# PDB.net
KiCad netlist of a schematic drawn in EAGLE
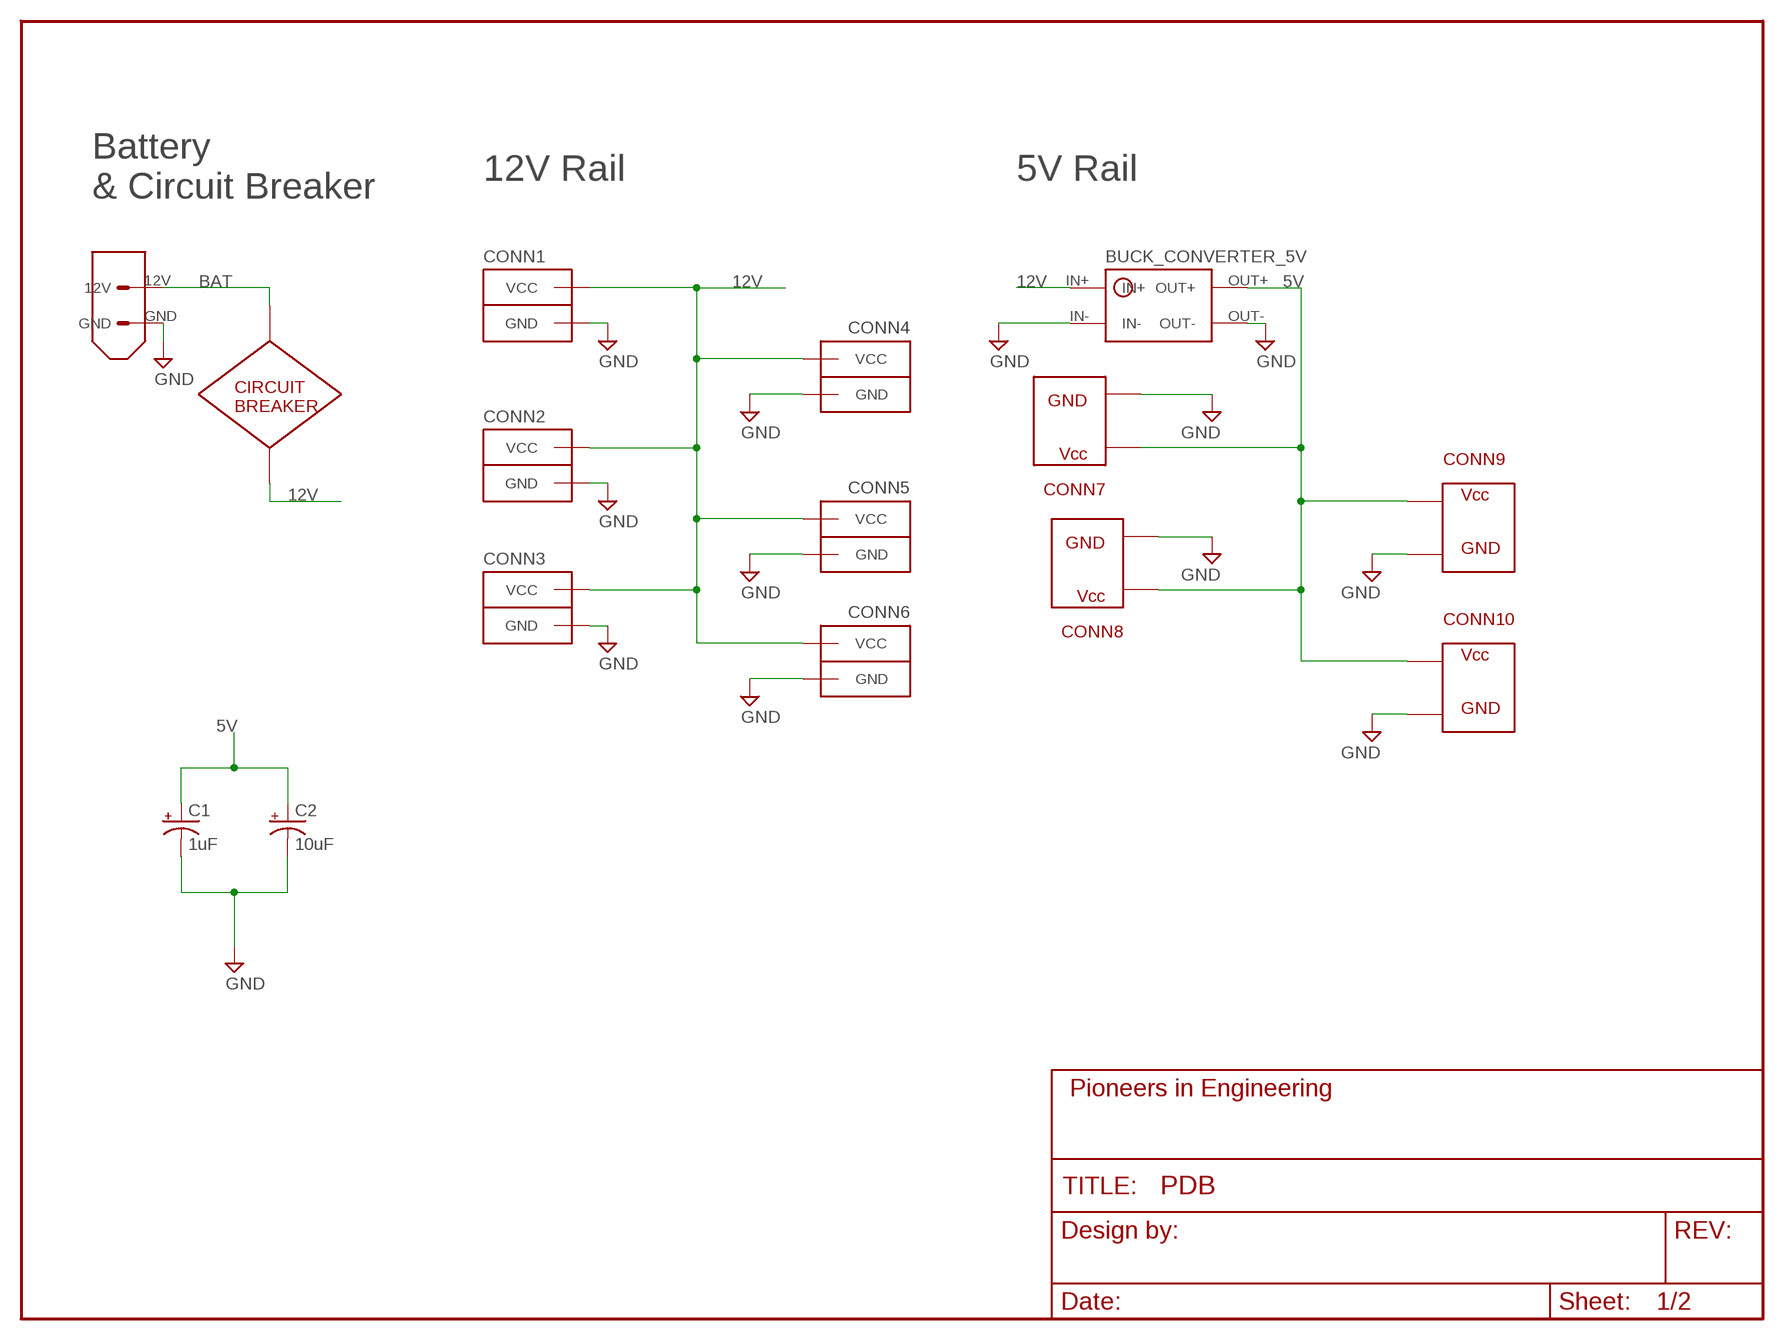
[diagram p0: schematic, sheet 1]
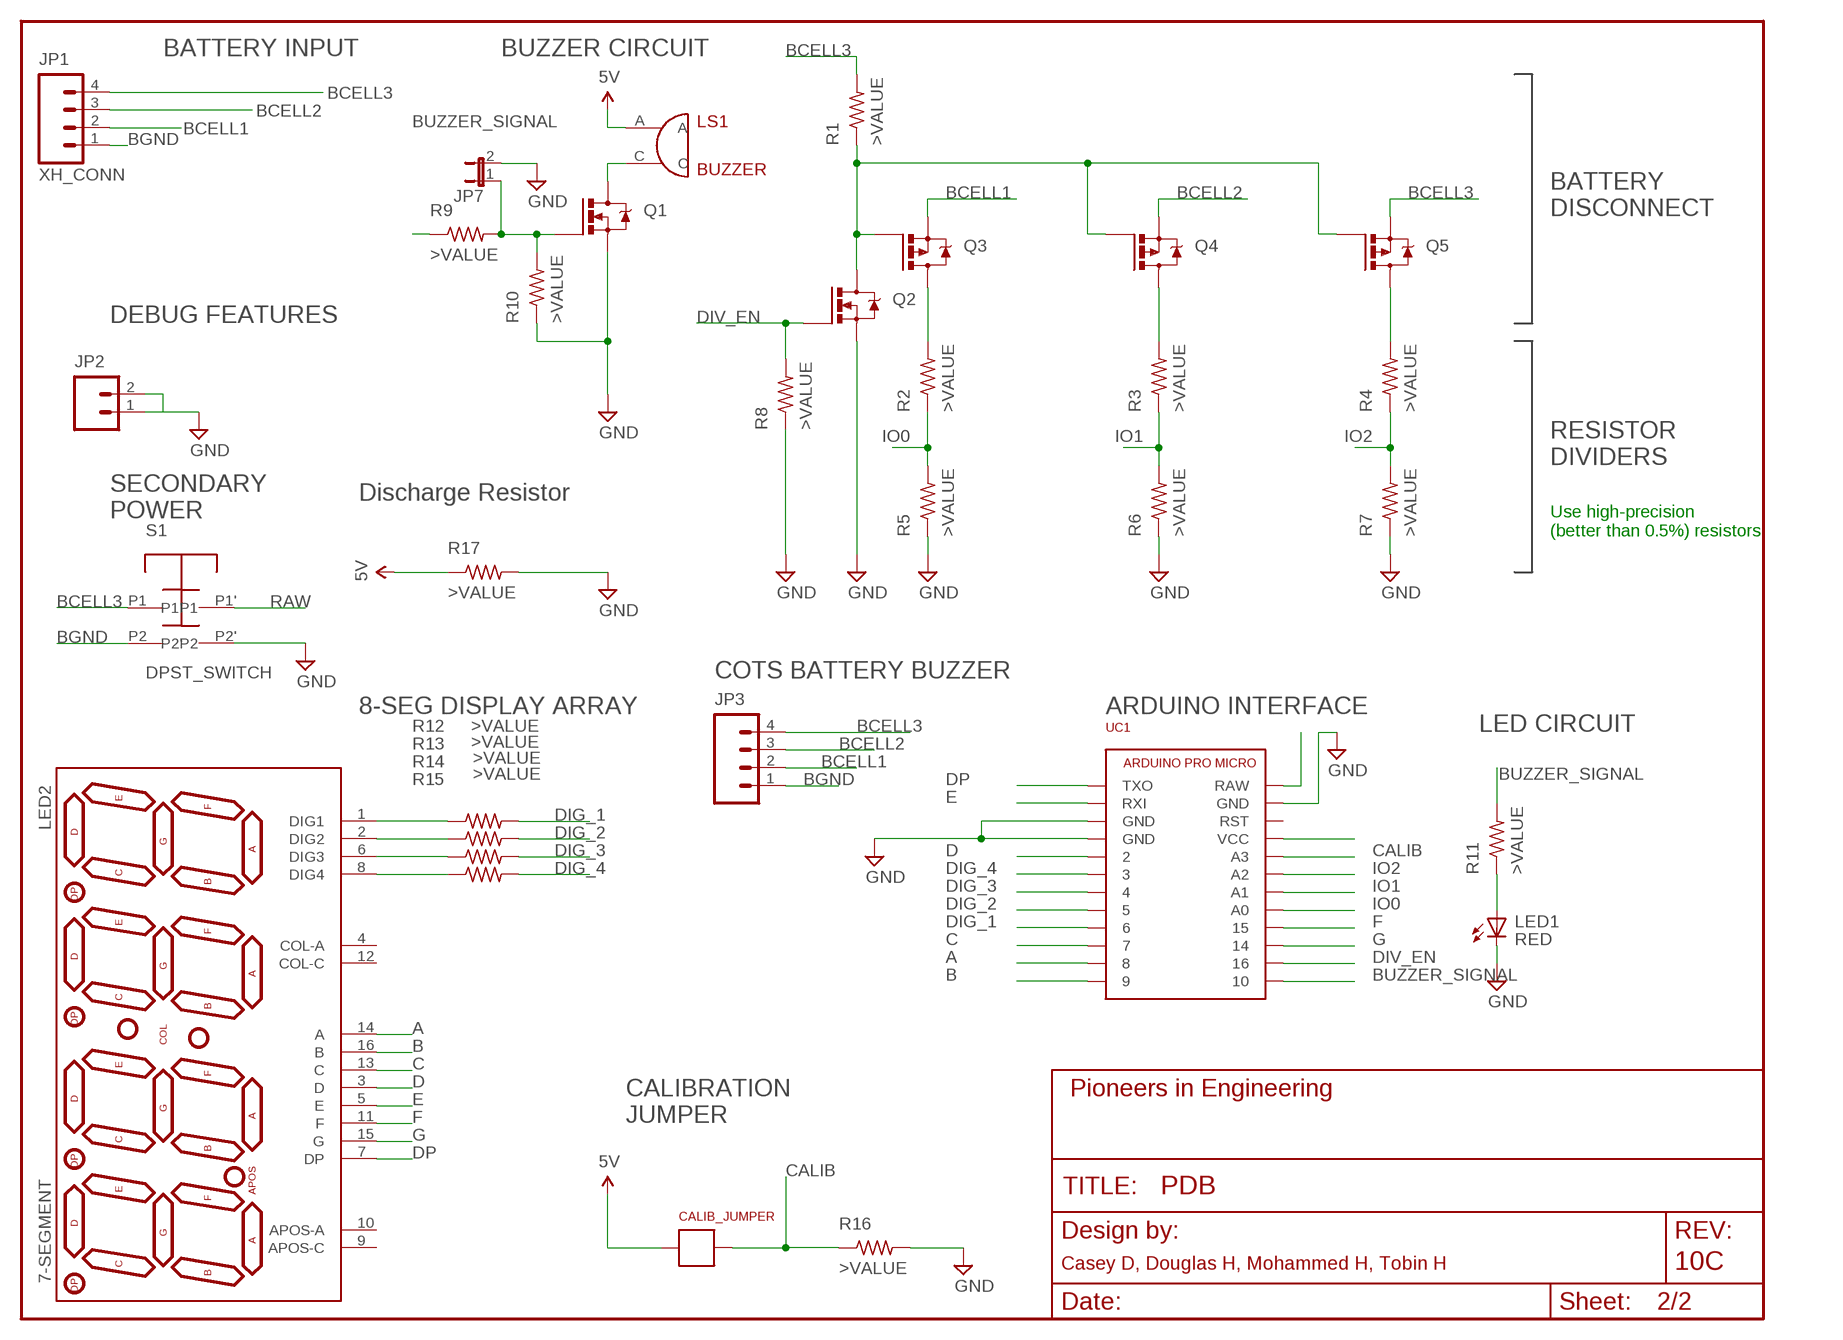
[diagram p1: schematic, sheet 2]

(export (version "E")
  (design (tool "Eeschema 10.0.6"))
  (components
    (comp (ref "CALIB_JUMPER")
      (value "JUMPER")
      (footprint "eagle-import:JUMPER")
      (fields
        (field (name "DISTRIBUTOR_PART_NUMBER") "952-2262-ND")
        (field (name "MANUFACTURER") "Harwin. Inc")
        (field (name "MANUFACTURER_PART_NUMBER") "M20-9990246")
      )
      (libsource (lib "eagle-import") (part "JUMPER"))
    )
    (comp (ref "JP1")
      (value "XH_CONN")
      (footprint "eagle-import:XH_CONNECTOR_4POS_2.5MM")
      (libsource (lib "eagle-import") (part "XH_CONNECTOR_4POS"))
    )
    (comp (ref "JP2")
      (value "M02PTH")
      (footprint "eagle-import:1X02")
      (libsource (lib "eagle-import") (part "M02PTH"))
    )
    (comp (ref "JP3")
      (value "M04PTH")
      (footprint "eagle-import:1X04")
      (libsource (lib "eagle-import") (part "M04PTH"))
    )
    (comp (ref "JP7")
      (value "JP1E")
      (footprint "eagle-import:JP1")
      (libsource (lib "eagle-import") (part "JP1E"))
    )
    (comp (ref "LED1")
      (value "RED")
      (footprint "eagle-import:LED-0805")
      (libsource (lib "eagle-import") (part "LED0805"))
    )
    (comp (ref "LED2")
      (value "7-SEGMENT")
      (footprint "eagle-import:7-SEGMENT-4DIGIT-YOUNGSUN")
      (libsource (lib "eagle-import") (part "7-SEGMENT-4DIGIT-YOUNGSUN"))
    )
    (comp (ref "LS1")
      (value "BUZZER")
      (footprint "eagle-import:BUZZER_MAGNETIC_5V_12MM_RADIAL")
      (libsource (lib "eagle-import") (part "BUZZER"))
    )
    (comp (ref "Q1")
      (value "NMOS")
      (footprint "eagle-import:SOT23-3")
      (libsource (lib "eagle-import") (part "N-CHANNEL-MOSFETSOT23-3"))
    )
    (comp (ref "Q2")
      (value "IRFML8244")
      (footprint "eagle-import:SOT23-3")
      (libsource (lib "eagle-import") (part "N-CHANNEL-MOSFETSOT23-3"))
    )
    (comp (ref "Q3")
      (value "PMOS")
      (footprint "eagle-import:SOT23-3")
      (libsource (lib "eagle-import") (part "P-CHANNEL-MOSFETSOT23-3"))
    )
    (comp (ref "Q4")
      (value "PMOS")
      (footprint "eagle-import:SOT23-3")
      (libsource (lib "eagle-import") (part "P-CHANNEL-MOSFETSOT23-3"))
    )
    (comp (ref "Q5")
      (value "PMOS")
      (footprint "eagle-import:SOT23-3")
      (libsource (lib "eagle-import") (part "P-CHANNEL-MOSFETSOT23-3"))
    )
    (comp (ref "R1")
      (value ">VALUE")
      (footprint "eagle-import:R0603")
      (fields (field (name "MANUFACTURER") "Rohm Semiconductor"))
      (libsource (lib "eagle-import") (part "R-US_R0603"))
    )
    (comp (ref "R2")
      (value ">VALUE")
      (footprint "eagle-import:R0603")
      (fields (field (name "MANUFACTURER") "Rohm Semiconductor"))
      (libsource (lib "eagle-import") (part "R-US_R0603"))
    )
    (comp (ref "R3")
      (value ">VALUE")
      (footprint "eagle-import:R0603")
      (fields (field (name "MANUFACTURER") "Rohm Semiconductor"))
      (libsource (lib "eagle-import") (part "R-US_R0603"))
    )
    (comp (ref "R4")
      (value ">VALUE")
      (footprint "eagle-import:R0603")
      (fields (field (name "MANUFACTURER") "Rohm Semiconductor"))
      (libsource (lib "eagle-import") (part "R-US_R0603"))
    )
    (comp (ref "R5")
      (value ">VALUE")
      (footprint "eagle-import:R0603")
      (fields (field (name "MANUFACTURER") "Rohm Semiconductor"))
      (libsource (lib "eagle-import") (part "R-US_R0603"))
    )
    (comp (ref "R6")
      (value ">VALUE")
      (footprint "eagle-import:R0603")
      (fields (field (name "MANUFACTURER") "Rohm Semiconductor"))
      (libsource (lib "eagle-import") (part "R-US_R0603"))
    )
    (comp (ref "R7")
      (value ">VALUE")
      (footprint "eagle-import:R0603")
      (fields (field (name "MANUFACTURER") "Rohm Semiconductor"))
      (libsource (lib "eagle-import") (part "R-US_R0603"))
    )
    (comp (ref "R8")
      (value ">VALUE")
      (footprint "eagle-import:R0603")
      (fields (field (name "MANUFACTURER") "Rohm Semiconductor"))
      (libsource (lib "eagle-import") (part "R-US_R0603"))
    )
    (comp (ref "R9")
      (value ">VALUE")
      (footprint "eagle-import:R0603")
      (fields (field (name "MANUFACTURER") "Rohm Semiconductor"))
      (libsource (lib "eagle-import") (part "R-US_R0603"))
    )
    (comp (ref "R10")
      (value ">VALUE")
      (footprint "eagle-import:R0603")
      (fields (field (name "MANUFACTURER") "Rohm Semiconductor"))
      (libsource (lib "eagle-import") (part "R-US_R0603"))
    )
    (comp (ref "R11")
      (value ">VALUE")
      (footprint "eagle-import:R0603")
      (fields (field (name "MANUFACTURER") "Rohm Semiconductor"))
      (libsource (lib "eagle-import") (part "R-US_R0603"))
    )
    (comp (ref "R12")
      (value ">VALUE")
      (footprint "eagle-import:R0603")
      (fields (field (name "MANUFACTURER") "Rohm Semiconductor"))
      (libsource (lib "eagle-import") (part "R-US_R0603"))
    )
    (comp (ref "R13")
      (value ">VALUE")
      (footprint "eagle-import:R0603")
      (fields (field (name "MANUFACTURER") "Rohm Semiconductor"))
      (libsource (lib "eagle-import") (part "R-US_R0603"))
    )
    (comp (ref "R14")
      (value ">VALUE")
      (footprint "eagle-import:R0603")
      (fields (field (name "MANUFACTURER") "Rohm Semiconductor"))
      (libsource (lib "eagle-import") (part "R-US_R0603"))
    )
    (comp (ref "R15")
      (value ">VALUE")
      (footprint "eagle-import:R0603")
      (fields (field (name "MANUFACTURER") "Rohm Semiconductor"))
      (libsource (lib "eagle-import") (part "R-US_R0603"))
    )
    (comp (ref "R16")
      (value ">VALUE")
      (footprint "eagle-import:R0603")
      (fields (field (name "MANUFACTURER") "Rohm Semiconductor"))
      (libsource (lib "eagle-import") (part "R-US_R0603"))
    )
    (comp (ref "R17")
      (value ">VALUE")
      (footprint "eagle-import:R0603")
      (fields (field (name "MANUFACTURER") "Rohm Semiconductor"))
      (libsource (lib "eagle-import") (part "R-US_R0603"))
    )
    (comp (ref "S1")
      (value "DPST_SWITCH")
      (footprint "eagle-import:C&K_SWITCH")
      (libsource (lib "eagle-import") (part "DPST_SWITCH"))
    )
    (comp (ref "UC1")
      (value "ARDUINO_PRO_MICRO")
      (footprint "eagle-import:ARDUINO_PRO_MICRO")
      (fields
        (field (name "DISTRIBUTOR_PART_NUMBER") "32284746884")
        (field (name "MANUFACTURER") "Feiyang electronics")
      )
      (libsource (lib "eagle-import") (part "ARDUINO_PRO_MICRO"))
    )
    (comp (ref "C1")
      (value "1uF")
      (footprint "eagle-import:E5-5")
      (libsource (lib "eagle-import") (part "CPOL-USE5-5"))
    )
    (comp (ref "C2")
      (value "10uF")
      (footprint "eagle-import:E5-5")
      (libsource (lib "eagle-import") (part "CPOL-USE5-5"))
    )
    (comp (ref "CIRCUIT_BREAKER")
      (value "CIRC_BREAKER")
      (footprint "eagle-import:CIRC_BREAKER")
      (libsource (lib "eagle-import") (part "CIRC_BREAKER"))
    )
    (comp (ref "CONN1")
      (value "ANDERSONVERTICAL")
      (footprint "eagle-import:ANDERSON_VERTICAL")
      (libsource (lib "eagle-import") (part "ANDERSONVERTICAL"))
    )
    (comp (ref "CONN2")
      (value "ANDERSONVERTICAL")
      (footprint "eagle-import:ANDERSON_VERTICAL")
      (libsource (lib "eagle-import") (part "ANDERSONVERTICAL"))
    )
    (comp (ref "CONN3")
      (value "ANDERSONVERTICAL")
      (footprint "eagle-import:ANDERSON_VERTICAL")
      (libsource (lib "eagle-import") (part "ANDERSONVERTICAL"))
    )
    (comp (ref "CONN4")
      (value "ANDERSONVERTICAL")
      (footprint "eagle-import:ANDERSON_VERTICAL")
      (libsource (lib "eagle-import") (part "ANDERSONVERTICAL"))
    )
    (comp (ref "CONN5")
      (value "ANDERSONVERTICAL")
      (footprint "eagle-import:ANDERSON_VERTICAL")
      (libsource (lib "eagle-import") (part "ANDERSONVERTICAL"))
    )
    (comp (ref "CONN6")
      (value "ANDERSONVERTICAL")
      (footprint "eagle-import:ANDERSON_VERTICAL")
      (libsource (lib "eagle-import") (part "ANDERSONVERTICAL"))
    )
    (comp (ref "CONN7")
      (value "ATX")
      (footprint "eagle-import:ATX")
      (libsource (lib "eagle-import") (part "ATX"))
    )
    (comp (ref "CONN8")
      (value "ATX")
      (footprint "eagle-import:ATX")
      (libsource (lib "eagle-import") (part "ATX"))
    )
    (comp (ref "CONN9")
      (value "ATX")
      (footprint "eagle-import:ATX")
      (libsource (lib "eagle-import") (part "ATX"))
    )
    (comp (ref "CONN10")
      (value "ATX")
      (footprint "eagle-import:ATX")
      (libsource (lib "eagle-import") (part "ATX"))
    )
    (comp (ref "U$1")
      (value "BUCK_CONVERTER_5V")
      (footprint "eagle-import:BUCK_CONVERTER_5V")
      (libsource (lib "eagle-import") (part "BUCK_CONVERTER_5V"))
    )
    (comp (ref "XT60")
      (value "XT60CONNECTOR")
      (footprint "eagle-import:XT60CONNECTOR")
      (fields (field (name "PARTNUMBER") "PRT-10474 "))
      (libsource (lib "eagle-import") (part "XT60CONNECTOR"))
    )
  )
  (nets
    (net (code "1") (name "5V") (class "Default")
      (node (ref "C1") (pin "+") (pinfunction "+_+") (pintype "passive"))
      (node (ref "C2") (pin "+") (pinfunction "+_+") (pintype "passive"))
      (node (ref "CALIB_JUMPER") (pin "P$1") (pinfunction "P$1_P$1") (pintype "input"))
      (node (ref "CONN10") (pin "P$1") (pinfunction "P$1_P$1") (pintype "power_in"))
      (node (ref "CONN7") (pin "P$1") (pinfunction "P$1_P$1") (pintype "power_in"))
      (node (ref "CONN8") (pin "P$1") (pinfunction "P$1_P$1") (pintype "power_in"))
      (node (ref "CONN9") (pin "P$1") (pinfunction "P$1_P$1") (pintype "power_in"))
      (node (ref "LS1") (pin "A") (pinfunction "A_A") (pintype "bidirectional"))
      (node (ref "R17") (pin "1") (pinfunction "1_1") (pintype "passive"))
      (node (ref "U$1") (pin "OUT+") (pinfunction "OUT+_OUT+") (pintype "bidirectional"))
      (node (ref "UC1") (pin "VCC") (pinfunction "VCC_VCC") (pintype "bidirectional"))
    )
    (net (code "2") (name "12V") (class "Default")
      (node (ref "CIRCUIT_BREAKER") (pin "P$2") (pinfunction "P$2_P$2") (pintype "bidirectional"))
      (node (ref "CONN1") (pin "PIN2") (pinfunction "VCC_PIN2") (pintype "bidirectional"))
      (node (ref "CONN2") (pin "PIN2") (pinfunction "VCC_PIN2") (pintype "bidirectional"))
      (node (ref "CONN3") (pin "PIN2") (pinfunction "VCC_PIN2") (pintype "bidirectional"))
      (node (ref "CONN4") (pin "PIN2") (pinfunction "VCC_PIN2") (pintype "bidirectional"))
      (node (ref "CONN5") (pin "PIN2") (pinfunction "VCC_PIN2") (pintype "bidirectional"))
      (node (ref "CONN6") (pin "PIN2") (pinfunction "VCC_PIN2") (pintype "bidirectional"))
      (node (ref "U$1") (pin "IN+") (pinfunction "IN+_IN+") (pintype "bidirectional"))
    )
    (net (code "3") (name "A") (class "Default")
      (node (ref "LED2") (pin "14") (pinfunction "A_14") (pintype "bidirectional"))
      (node (ref "UC1") (pin "8") (pinfunction "8_8") (pintype "bidirectional"))
    )
    (net (code "4") (name "B") (class "Default")
      (node (ref "LED2") (pin "16") (pinfunction "B_16") (pintype "bidirectional"))
      (node (ref "UC1") (pin "9") (pinfunction "9_9") (pintype "bidirectional"))
    )
    (net (code "5") (name "BAT") (class "Default")
      (node (ref "CIRCUIT_BREAKER") (pin "P$1") (pinfunction "P$1_P$1") (pintype "bidirectional"))
      (node (ref "XT60") (pin "12V") (pinfunction "12V_12V") (pintype "bidirectional"))
    )
    (net (code "6") (name "BCELL1") (class "Default")
      (node (ref "JP1") (pin "2") (pinfunction "2_2") (pintype "passive"))
      (node (ref "JP3") (pin "2") (pinfunction "2_2") (pintype "passive"))
      (node (ref "Q3") (pin "2") (pinfunction "S_2") (pintype "passive"))
    )
    (net (code "7") (name "BCELL2") (class "Default")
      (node (ref "JP1") (pin "3") (pinfunction "3_3") (pintype "passive"))
      (node (ref "JP3") (pin "3") (pinfunction "3_3") (pintype "passive"))
      (node (ref "Q4") (pin "2") (pinfunction "S_2") (pintype "passive"))
    )
    (net (code "8") (name "BCELL3") (class "Default")
      (node (ref "JP1") (pin "4") (pinfunction "4_4") (pintype "passive"))
      (node (ref "JP3") (pin "4") (pinfunction "4_4") (pintype "passive"))
      (node (ref "Q5") (pin "2") (pinfunction "S_2") (pintype "passive"))
      (node (ref "R1") (pin "2") (pinfunction "2_2") (pintype "passive"))
      (node (ref "S1") (pin "P1") (pinfunction "P1_P1") (pintype "bidirectional"))
    )
    (net (code "9") (name "BGND") (class "Default")
      (node (ref "JP1") (pin "1") (pinfunction "1_1") (pintype "passive"))
      (node (ref "JP3") (pin "1") (pinfunction "1_1") (pintype "passive"))
      (node (ref "S1") (pin "P2") (pinfunction "P2_P2") (pintype "bidirectional"))
    )
    (net (code "10") (name "BUZZER_SIGNAL") (class "Default")
      (node (ref "R11") (pin "2") (pinfunction "2_2") (pintype "passive"))
      (node (ref "R9") (pin "1") (pinfunction "1_1") (pintype "passive"))
      (node (ref "UC1") (pin "10") (pinfunction "10_10") (pintype "bidirectional"))
    )
    (net (code "11") (name "C") (class "Default")
      (node (ref "LED2") (pin "13") (pinfunction "C_13") (pintype "bidirectional"))
      (node (ref "UC1") (pin "7") (pinfunction "7_7") (pintype "bidirectional"))
    )
    (net (code "12") (name "CALIB") (class "Default")
      (node (ref "CALIB_JUMPER") (pin "P$2") (pinfunction "P$2_P$2") (pintype "bidirectional"))
      (node (ref "R16") (pin "1") (pinfunction "1_1") (pintype "passive"))
      (node (ref "UC1") (pin "A3") (pinfunction "A3_A3") (pintype "bidirectional"))
    )
    (net (code "13") (name "D") (class "Default")
      (node (ref "LED2") (pin "3") (pinfunction "D_3") (pintype "bidirectional"))
      (node (ref "UC1") (pin "2") (pinfunction "2_2") (pintype "bidirectional"))
    )
    (net (code "14") (name "DIG_1") (class "Default")
      (node (ref "R12") (pin "2") (pinfunction "2_2") (pintype "passive"))
      (node (ref "UC1") (pin "6") (pinfunction "6_6") (pintype "bidirectional"))
    )
    (net (code "15") (name "DIG_2") (class "Default")
      (node (ref "R13") (pin "2") (pinfunction "2_2") (pintype "passive"))
      (node (ref "UC1") (pin "5") (pinfunction "5_5") (pintype "bidirectional"))
    )
    (net (code "16") (name "DIG_3") (class "Default")
      (node (ref "R14") (pin "2") (pinfunction "2_2") (pintype "passive"))
      (node (ref "UC1") (pin "4") (pinfunction "4_4") (pintype "bidirectional"))
    )
    (net (code "17") (name "DIG_4") (class "Default")
      (node (ref "R15") (pin "2") (pinfunction "2_2") (pintype "passive"))
      (node (ref "UC1") (pin "3") (pinfunction "3_3") (pintype "bidirectional"))
    )
    (net (code "18") (name "DIV_EN") (class "Default")
      (node (ref "Q2") (pin "1") (pinfunction "G_1") (pintype "passive"))
      (node (ref "R8") (pin "2") (pinfunction "2_2") (pintype "passive"))
      (node (ref "UC1") (pin "16") (pinfunction "16_16") (pintype "bidirectional"))
    )
    (net (code "19") (name "DP") (class "Default")
      (node (ref "LED2") (pin "7") (pinfunction "DP_7") (pintype "bidirectional"))
      (node (ref "UC1") (pin "TXO") (pinfunction "TXO_TXO") (pintype "bidirectional"))
    )
    (net (code "20") (name "E") (class "Default")
      (node (ref "LED2") (pin "5") (pinfunction "E_5") (pintype "bidirectional"))
      (node (ref "UC1") (pin "RXI") (pinfunction "RXI_RXI") (pintype "bidirectional"))
    )
    (net (code "21") (name "F") (class "Default")
      (node (ref "LED2") (pin "11") (pinfunction "F_11") (pintype "bidirectional"))
      (node (ref "UC1") (pin "15") (pinfunction "15_15") (pintype "bidirectional"))
    )
    (net (code "22") (name "G") (class "Default")
      (node (ref "LED2") (pin "15") (pinfunction "G_15") (pintype "bidirectional"))
      (node (ref "UC1") (pin "14") (pinfunction "14_14") (pintype "bidirectional"))
    )
    (net (code "23") (name "GND") (class "Default")
      (node (ref "C1") (pin "-") (pinfunction "-_-") (pintype "passive"))
      (node (ref "C2") (pin "-") (pinfunction "-_-") (pintype "passive"))
      (node (ref "CONN1") (pin "PIN1") (pinfunction "GND_PIN1") (pintype "bidirectional"))
      (node (ref "CONN10") (pin "P$2") (pinfunction "P$2_P$2") (pintype "power_in"))
      (node (ref "CONN2") (pin "PIN1") (pinfunction "GND_PIN1") (pintype "bidirectional"))
      (node (ref "CONN3") (pin "PIN1") (pinfunction "GND_PIN1") (pintype "bidirectional"))
      (node (ref "CONN4") (pin "PIN1") (pinfunction "GND_PIN1") (pintype "bidirectional"))
      (node (ref "CONN5") (pin "PIN1") (pinfunction "GND_PIN1") (pintype "bidirectional"))
      (node (ref "CONN6") (pin "PIN1") (pinfunction "GND_PIN1") (pintype "bidirectional"))
      (node (ref "CONN7") (pin "P$2") (pinfunction "P$2_P$2") (pintype "power_in"))
      (node (ref "CONN8") (pin "P$2") (pinfunction "P$2_P$2") (pintype "power_in"))
      (node (ref "CONN9") (pin "P$2") (pinfunction "P$2_P$2") (pintype "power_in"))
      (node (ref "JP2") (pin "1") (pinfunction "1_1") (pintype "passive"))
      (node (ref "JP2") (pin "2") (pinfunction "2_2") (pintype "passive"))
      (node (ref "JP7") (pin "2") (pinfunction "2_2") (pintype "passive"))
      (node (ref "LED1") (pin "C") (pinfunction "C_C") (pintype "passive"))
      (node (ref "Q1") (pin "2") (pinfunction "S_2") (pintype "passive"))
      (node (ref "Q2") (pin "2") (pinfunction "S_2") (pintype "passive"))
      (node (ref "R10") (pin "1") (pinfunction "1_1") (pintype "passive"))
      (node (ref "R16") (pin "2") (pinfunction "2_2") (pintype "passive"))
      (node (ref "R17") (pin "2") (pinfunction "2_2") (pintype "passive"))
      (node (ref "R5") (pin "1") (pinfunction "1_1") (pintype "passive"))
      (node (ref "R6") (pin "1") (pinfunction "1_1") (pintype "passive"))
      (node (ref "R7") (pin "1") (pinfunction "1_1") (pintype "passive"))
      (node (ref "R8") (pin "1") (pinfunction "1_1") (pintype "passive"))
      (node (ref "S1") (pin "P2'") (pinfunction "P2'_P2'") (pintype "bidirectional"))
      (node (ref "U$1") (pin "IN-") (pinfunction "IN-_IN-") (pintype "bidirectional"))
      (node (ref "U$1") (pin "OUT-") (pinfunction "OUT-_OUT-") (pintype "bidirectional"))
      (node (ref "UC1") (pin "GND@0") (pinfunction "GND_GND@0") (pintype "bidirectional"))
      (node (ref "UC1") (pin "GND@1") (pinfunction "GND_GND@1") (pintype "bidirectional"))
      (node (ref "UC1") (pin "GND@2") (pinfunction "GND_GND@2") (pintype "bidirectional"))
      (node (ref "XT60") (pin "GND") (pinfunction "GND_GND") (pintype "bidirectional"))
    )
    (net (code "24") (name "IO0") (class "Default")
      (node (ref "R2") (pin "1") (pinfunction "1_1") (pintype "passive"))
      (node (ref "R5") (pin "2") (pinfunction "2_2") (pintype "passive"))
      (node (ref "UC1") (pin "A0") (pinfunction "A0_A0") (pintype "bidirectional"))
    )
    (net (code "25") (name "IO1") (class "Default")
      (node (ref "R3") (pin "1") (pinfunction "1_1") (pintype "passive"))
      (node (ref "R6") (pin "2") (pinfunction "2_2") (pintype "passive"))
      (node (ref "UC1") (pin "A1") (pinfunction "A1_A1") (pintype "bidirectional"))
    )
    (net (code "26") (name "IO2") (class "Default")
      (node (ref "R4") (pin "1") (pinfunction "1_1") (pintype "passive"))
      (node (ref "R7") (pin "2") (pinfunction "2_2") (pintype "passive"))
      (node (ref "UC1") (pin "A2") (pinfunction "A2_A2") (pintype "bidirectional"))
    )
    (net (code "27") (name "Net-(LED1-PadA)") (class "Default")
      (node (ref "LED1") (pin "A") (pinfunction "A_A") (pintype "passive"))
      (node (ref "R11") (pin "1") (pinfunction "1_1") (pintype "passive"))
    )
    (net (code "28") (name "Net-(LED2-DIG1)") (class "Default")
      (node (ref "LED2") (pin "1") (pinfunction "DIG1_1") (pintype "bidirectional"))
      (node (ref "R12") (pin "1") (pinfunction "1_1") (pintype "passive"))
    )
    (net (code "29") (name "Net-(LED2-DIG2)") (class "Default")
      (node (ref "LED2") (pin "2") (pinfunction "DIG2_2") (pintype "bidirectional"))
      (node (ref "R13") (pin "1") (pinfunction "1_1") (pintype "passive"))
    )
    (net (code "30") (name "Net-(LED2-DIG3)") (class "Default")
      (node (ref "LED2") (pin "6") (pinfunction "DIG3_6") (pintype "bidirectional"))
      (node (ref "R14") (pin "1") (pinfunction "1_1") (pintype "passive"))
    )
    (net (code "31") (name "Net-(LED2-DIG4)") (class "Default")
      (node (ref "LED2") (pin "8") (pinfunction "DIG4_8") (pintype "bidirectional"))
      (node (ref "R15") (pin "1") (pinfunction "1_1") (pintype "passive"))
    )
    (net (code "32") (name "Net-(Q1-D)") (class "Default")
      (node (ref "LS1") (pin "C") (pinfunction "C_C") (pintype "bidirectional"))
      (node (ref "Q1") (pin "3") (pinfunction "D_3") (pintype "passive"))
    )
    (net (code "33") (name "Net-(Q1-G)") (class "Default")
      (node (ref "JP7") (pin "1") (pinfunction "1_1") (pintype "passive"))
      (node (ref "Q1") (pin "1") (pinfunction "G_1") (pintype "passive"))
      (node (ref "R10") (pin "2") (pinfunction "2_2") (pintype "passive"))
      (node (ref "R9") (pin "2") (pinfunction "2_2") (pintype "passive"))
    )
    (net (code "34") (name "Net-(Q2-D)") (class "Default")
      (node (ref "Q2") (pin "3") (pinfunction "D_3") (pintype "passive"))
      (node (ref "Q3") (pin "1") (pinfunction "G_1") (pintype "passive"))
      (node (ref "Q4") (pin "1") (pinfunction "G_1") (pintype "passive"))
      (node (ref "Q5") (pin "1") (pinfunction "G_1") (pintype "passive"))
      (node (ref "R1") (pin "1") (pinfunction "1_1") (pintype "passive"))
    )
    (net (code "35") (name "Net-(Q3-D)") (class "Default")
      (node (ref "Q3") (pin "3") (pinfunction "D_3") (pintype "passive"))
      (node (ref "R2") (pin "2") (pinfunction "2_2") (pintype "passive"))
    )
    (net (code "36") (name "Net-(Q4-D)") (class "Default")
      (node (ref "Q4") (pin "3") (pinfunction "D_3") (pintype "passive"))
      (node (ref "R3") (pin "2") (pinfunction "2_2") (pintype "passive"))
    )
    (net (code "37") (name "Net-(Q5-D)") (class "Default")
      (node (ref "Q5") (pin "3") (pinfunction "D_3") (pintype "passive"))
      (node (ref "R4") (pin "2") (pinfunction "2_2") (pintype "passive"))
    )
    (net (code "38") (name "RAW") (class "Default")
      (node (ref "S1") (pin "P1'") (pinfunction "P1'_P1'") (pintype "bidirectional"))
      (node (ref "UC1") (pin "RAW") (pinfunction "RAW_RAW") (pintype "bidirectional"))
    )
    (net (code "39") (name "unconnected-(LED2-APOS-A-Pad10)") (class "Default")
      (node (ref "LED2") (pin "10") (pinfunction "APOS-A_10") (pintype "bidirectional"))
    )
    (net (code "40") (name "unconnected-(LED2-APOS-C-Pad9)") (class "Default")
      (node (ref "LED2") (pin "9") (pinfunction "APOS-C_9") (pintype "bidirectional"))
    )
    (net (code "41") (name "unconnected-(LED2-COL-A-Pad4)") (class "Default")
      (node (ref "LED2") (pin "4") (pinfunction "COL-A_4") (pintype "bidirectional"))
    )
    (net (code "42") (name "unconnected-(LED2-COL-C-Pad12)") (class "Default")
      (node (ref "LED2") (pin "12") (pinfunction "COL-C_12") (pintype "bidirectional"))
    )
    (net (code "43") (name "unconnected-(UC1-PadRST)") (class "Default")
      (node (ref "UC1") (pin "RST") (pinfunction "RST_RST") (pintype "bidirectional"))
    )
  )
)
